# ADC.net
KiCad netlist of a schematic drawn in Altium Designer
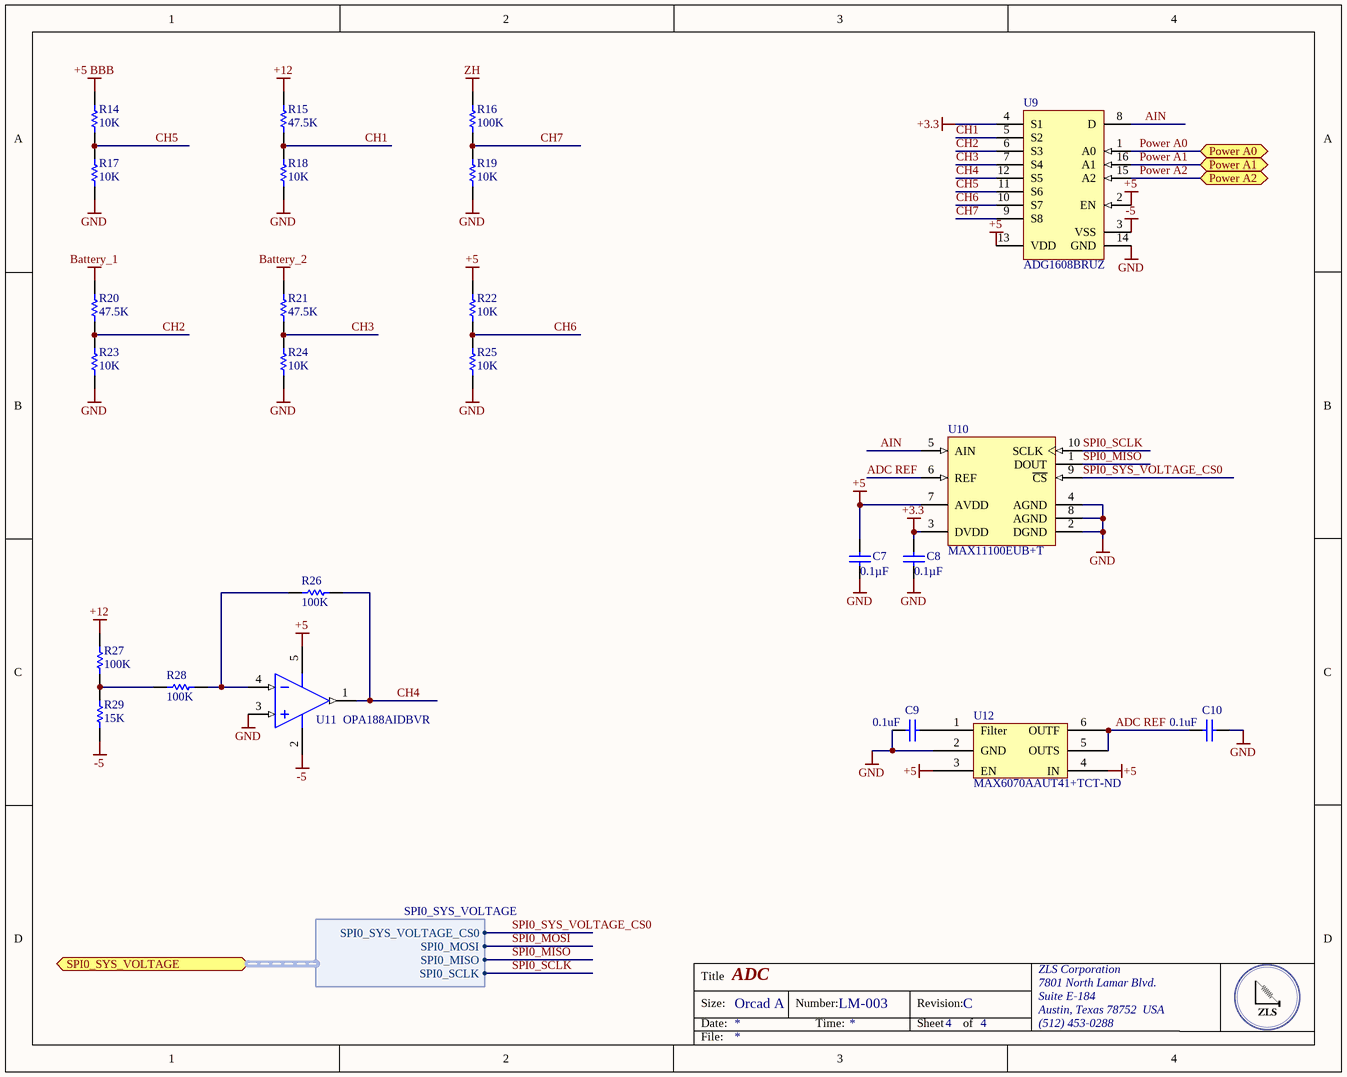
[diagram p0: ADC.SchDoc]

(export (version "E")
  (design (tool "Eeschema 10.0.6"))
  (components
    (comp (ref "C7")
      (value "CAP CER 0.1UF 25V X7R 0805")
      (footprint "CAPC0805(2012)145_N")
      (fields
        (field (name "MANUFACTURER") "Murata Electronics North America")
        (field (name "MANUFACTURER PART NUMBER") "GRM21BR71E104KA01L")
        (field (name "CAPACITANCE") "0.1µF")
        (field (name "TOLERANCE") "±10%")
      )
      (libsource (lib "Altium Content Vault") (part "CMP-1036-04795-1"))
    )
    (comp (ref "C8")
      (value "CAP CER 0.1UF 25V X7R 0805")
      (footprint "CAPC0805(2012)145_N")
      (fields
        (field (name "MANUFACTURER") "Murata Electronics North America")
        (field (name "MANUFACTURER PART NUMBER") "GRM21BR71E104KA01L")
        (field (name "CAPACITANCE") "0.1µF")
        (field (name "TOLERANCE") "±10%")
      )
      (libsource (lib "Altium Content Vault") (part "CMP-1036-04795-1"))
    )
    (comp (ref "C9")
      (value "0.1uF")
      (footprint "CAPC0402(1005)60_L")
      (description "CAP CER 0.1UF 10V X7R 0402")
      (fields
        (field (name "MANUFACTURER") "Murata Electronics North America")
        (field (name "MANUFACTURER PART NUMBER") "GRM155R71A104KA01D")
      )
      (libsource (lib "Altium Content Vault") (part "CMP-1034-00252-1"))
    )
    (comp (ref "C10")
      (value "0.1uF")
      (footprint "CAPC0402(1005)60_L")
      (description "CAP CER 0.1UF 10V X7R 0402")
      (fields
        (field (name "MANUFACTURER") "Murata Electronics North America")
        (field (name "MANUFACTURER PART NUMBER") "GRM155R71A104KA01D")
      )
      (libsource (lib "Altium Content Vault") (part "CMP-1034-00252-1"))
    )
    (comp (ref "R14")
      (value "10K")
      (footprint "RESC0805(2012)_L")
      (description "RES SMD 10K OHM 1% 1/8W 0805")
      (fields
        (field (name "MANUFACTURER") "Yageo")
        (field (name "MANUFACTURER PART NUMBER") "AT0603FRE0710KL")
      )
      (libsource (lib "Altium Content Vault") (part "CMP-1013-00215-1"))
    )
    (comp (ref "R15")
      (value "47.5K")
      (footprint "RESC0805(2012)_L")
      (description "RES SMD 47.5K OHM 1% 1/10W 0805")
      (fields
        (field (name "MANUFACTURER") "Yageo")
        (field (name "MANUFACTURER PART NUMBER") "RT0603FRE0747K5L")
      )
      (libsource (lib "Altium Content Vault") (part "CMP-1013-00215-1"))
    )
    (comp (ref "R16")
      (value "100K")
      (footprint "RESC0805(2012)_L")
      (description "RES SMD 100K OHM 1% 1/10W 0805")
      (fields
        (field (name "MANUFACTURER") "Vishay Beyschlag")
        (field (name "MANUFACTURER PART NUMBER") "MCS04020C1003FE000")
      )
      (libsource (lib "Altium Content Vault") (part "CMP-1013-00215-1"))
    )
    (comp (ref "R17")
      (value "10K")
      (footprint "RESC0805(2012)_L")
      (description "RES SMD 10K OHM 1% 1/8W 0805")
      (fields
        (field (name "MANUFACTURER") "Yageo")
        (field (name "MANUFACTURER PART NUMBER") "AT0603FRE0710KL")
      )
      (libsource (lib "Altium Content Vault") (part "CMP-1013-00215-1"))
    )
    (comp (ref "R18")
      (value "10K")
      (footprint "RESC0805(2012)_L")
      (description "RES SMD 10K OHM 1% 1/8W 0805")
      (fields
        (field (name "MANUFACTURER") "Yageo")
        (field (name "MANUFACTURER PART NUMBER") "AT0603FRE0710KL")
      )
      (libsource (lib "Altium Content Vault") (part "CMP-1013-00215-1"))
    )
    (comp (ref "R19")
      (value "10K")
      (footprint "RESC0805(2012)_L")
      (description "RES SMD 10K OHM 1% 1/8W 0805")
      (fields
        (field (name "MANUFACTURER") "Yageo")
        (field (name "MANUFACTURER PART NUMBER") "AT0603FRE0710KL")
      )
      (libsource (lib "Altium Content Vault") (part "CMP-1013-00215-1"))
    )
    (comp (ref "R20")
      (value "47.5K")
      (footprint "RESC0805(2012)_L")
      (description "RES SMD 47.5K OHM 1% 1/10W 0805")
      (fields
        (field (name "MANUFACTURER") "Yageo")
        (field (name "MANUFACTURER PART NUMBER") "RT0603FRE0747K5L")
      )
      (libsource (lib "Altium Content Vault") (part "CMP-1013-00215-1"))
    )
    (comp (ref "R21")
      (value "47.5K")
      (footprint "RESC0805(2012)_L")
      (description "RES SMD 47.5K OHM 1% 1/10W 0805")
      (fields
        (field (name "MANUFACTURER") "Yageo")
        (field (name "MANUFACTURER PART NUMBER") "RT0603FRE0747K5L")
      )
      (libsource (lib "Altium Content Vault") (part "CMP-1013-00215-1"))
    )
    (comp (ref "R22")
      (value "10K")
      (footprint "RESC0805(2012)_L")
      (description "RES SMD 10K OHM 1% 1/8W 0805")
      (fields
        (field (name "MANUFACTURER") "Yageo")
        (field (name "MANUFACTURER PART NUMBER") "AT0603FRE0710KL")
      )
      (libsource (lib "Altium Content Vault") (part "CMP-1013-00215-1"))
    )
    (comp (ref "R23")
      (value "10K")
      (footprint "RESC0805(2012)_L")
      (description "RES SMD 10K OHM 1% 1/8W 0805")
      (fields
        (field (name "MANUFACTURER") "Yageo")
        (field (name "MANUFACTURER PART NUMBER") "AT0603FRE0710KL")
      )
      (libsource (lib "Altium Content Vault") (part "CMP-1013-00215-1"))
    )
    (comp (ref "R24")
      (value "10K")
      (footprint "RESC0805(2012)_L")
      (description "RES SMD 10K OHM 1% 1/8W 0805")
      (fields
        (field (name "MANUFACTURER") "Yageo")
        (field (name "MANUFACTURER PART NUMBER") "AT0603FRE0710KL")
      )
      (libsource (lib "Altium Content Vault") (part "CMP-1013-00215-1"))
    )
    (comp (ref "R25")
      (value "10K")
      (footprint "RESC0805(2012)_L")
      (description "RES SMD 10K OHM 1% 1/8W 0805")
      (fields
        (field (name "MANUFACTURER") "Yageo")
        (field (name "MANUFACTURER PART NUMBER") "AT0603FRE0710KL")
      )
      (libsource (lib "Altium Content Vault") (part "CMP-1013-00215-1"))
    )
    (comp (ref "R26")
      (value "100K")
      (footprint "RESC0805(2012)_L")
      (description "RES SMD 100K OHM 1% 1/10W 0805")
      (fields
        (field (name "MANUFACTURER") "Vishay Beyschlag")
        (field (name "MANUFACTURER PART NUMBER") "MCS04020C1003FE000")
      )
      (libsource (lib "Altium Content Vault") (part "CMP-1013-00215-1"))
    )
    (comp (ref "R27")
      (value "100K")
      (footprint "RESC0805(2012)_L")
      (description "RES SMD 100K OHM 1% 1/10W 0805")
      (fields
        (field (name "MANUFACTURER") "Vishay Beyschlag")
        (field (name "MANUFACTURER PART NUMBER") "MCS04020C1003FE000")
      )
      (libsource (lib "Altium Content Vault") (part "CMP-1013-00215-1"))
    )
    (comp (ref "R28")
      (value "100K")
      (footprint "RESC0805(2012)_L")
      (description "RES SMD 100K OHM 1% 1/10W 0805")
      (fields
        (field (name "MANUFACTURER") "Vishay Beyschlag")
        (field (name "MANUFACTURER PART NUMBER") "MCS04020C1003FE000")
      )
      (libsource (lib "Altium Content Vault") (part "CMP-1013-00215-1"))
    )
    (comp (ref "R29")
      (value "15K")
      (footprint "RESC0805(2012)_L")
      (description "RES SMD 15K OHM 1% 1/10W 0805")
      (fields
        (field (name "MANUFACTURER") "Vishay Beyschlag")
        (field (name "MANUFACTURER PART NUMBER") "MCS04020C1502FE000")
      )
      (libsource (lib "Altium Content Vault") (part "CMP-1013-00215-1"))
    )
    (comp (ref "U9")
      (value "ADG1608BRUZ")
      (footprint "ADI-RU-16_M")
      (description "4.5 Ohm Ron, 8-Channel +/-5 V,+12 V, +5 V and +3.3 V Multiplexer, 16-pin SOP (RU-16), Tube")
      (fields (field (name "MANUFACTURER") "Analog Devices Inc.") (field (name "BASE PART NUMBER") "ADG1608"))
      (libsource (lib "Altium Content Vault") (part "CMP-0793-00136-1"))
    )
    (comp (ref "U10")
      (value "MAX11100EUB+T")
      (footprint "U10+2_L")
      (description "IC ADC 16BIT SRL 200KSPS 10UMAX")
      (fields
        (field (name "MANUFACTURER") "Maxim Integrated")
        (field (name "MANUFACTURER PART NUMBER") "MAX11100EUB+")
      )
      (libsource (lib "Altium Content Vault") (part "CMP-0249-00017-1"))
    )
    (comp (ref "U11")
      (value "OPA188AIDBVR")
      (footprint "DBV0005A_M")
      (fields (field (name "MANUFACTURER") "Texas Instruments"))
      (libsource (lib "Altium Content Vault") (part "CMP-0809-00005-2"))
    )
    (comp (ref "U12")
      (value "MAX6070AAUT41+T")
      (footprint "SOT95P280X445-6N")
      (description "IC VREF SERIES 4.096V SOT23")
      (fields
        (field (name "SUPPLIER PART NUMBER 1") "MAX6070AAUT41+TCT-ND")
        (field (name "MANUFACTURER") "Maxim Integrated")
        (field (name "TOLERANCE") "±0.04%")
      )
      (libsource (lib "ZLS_Schematic_lib") (part "MAX6070AAUT41+T"))
    )
  )
  (nets
    (net (code "2") (name "+3.3") (class "Default")
      (node (ref "C8") (pin "1") (pinfunction "1_1") (pintype "passive"))
      (node (ref "U10") (pin "3") (pinfunction "DVDD_3") (pintype "power_in"))
      (node (ref "U9") (pin "4") (pinfunction "S1_4") (pintype "passive"))
    )
    (net (code "3") (name "+5") (class "Default")
      (node (ref "C7") (pin "1") (pinfunction "1_1") (pintype "passive"))
      (node (ref "R22") (pin "1") (pinfunction "1_1") (pintype "passive"))
      (node (ref "U10") (pin "7") (pinfunction "AVDD_7") (pintype "power_in"))
      (node (ref "U11") (pin "5") (pinfunction "V+_5") (pintype "power_in"))
      (node (ref "U12") (pin "3") (pinfunction "EN_3") (pintype "passive"))
      (node (ref "U12") (pin "4") (pinfunction "IN_4") (pintype "passive"))
      (node (ref "U9") (pin "13") (pinfunction "VDD_13") (pintype "power_in"))
      (node (ref "U9") (pin "2") (pinfunction "EN_2") (pintype "input"))
    )
    (net (code "4") (name "+5 BBB") (class "Default")
      (node (ref "R14") (pin "1") (pinfunction "1_1") (pintype "passive"))
    )
    (net (code "5") (name "+12") (class "Default")
      (node (ref "R15") (pin "1") (pinfunction "1_1") (pintype "passive"))
      (node (ref "R27") (pin "1") (pinfunction "1_1") (pintype "passive"))
    )
    (net (code "6") (name "-5") (class "Default")
      (node (ref "R29") (pin "2") (pinfunction "2_2") (pintype "passive"))
      (node (ref "U11") (pin "2") (pinfunction "V-_2") (pintype "power_in"))
      (node (ref "U9") (pin "3") (pinfunction "VSS_3") (pintype "power_in"))
    )
    (net (code "7") (name "/ADC REF") (class "Default")
      (node (ref "C10") (pin "2") (pinfunction "2_2") (pintype "passive"))
      (node (ref "U10") (pin "6") (pinfunction "REF_6") (pintype "input"))
      (node (ref "U12") (pin "5") (pinfunction "OUTS_5") (pintype "passive"))
      (node (ref "U12") (pin "6") (pinfunction "OUTF_6") (pintype "passive"))
    )
    (net (code "8") (name "/AIN") (class "Default")
      (node (ref "U10") (pin "5") (pinfunction "AIN_5") (pintype "input"))
      (node (ref "U9") (pin "8") (pinfunction "D_8") (pintype "passive"))
    )
    (net (code "9") (name "/CH1") (class "Default")
      (node (ref "R15") (pin "2") (pinfunction "2_2") (pintype "passive"))
      (node (ref "R18") (pin "1") (pinfunction "1_1") (pintype "passive"))
      (node (ref "U9") (pin "5") (pinfunction "S2_5") (pintype "passive"))
    )
    (net (code "10") (name "/CH2") (class "Default")
      (node (ref "R20") (pin "2") (pinfunction "2_2") (pintype "passive"))
      (node (ref "R23") (pin "1") (pinfunction "1_1") (pintype "passive"))
      (node (ref "U9") (pin "6") (pinfunction "S3_6") (pintype "passive"))
    )
    (net (code "11") (name "/CH3") (class "Default")
      (node (ref "R21") (pin "2") (pinfunction "2_2") (pintype "passive"))
      (node (ref "R24") (pin "1") (pinfunction "1_1") (pintype "passive"))
      (node (ref "U9") (pin "7") (pinfunction "S4_7") (pintype "passive"))
    )
    (net (code "12") (name "/CH4") (class "Default")
      (node (ref "R26") (pin "2") (pinfunction "2_2") (pintype "passive"))
      (node (ref "U11") (pin "1") (pinfunction "OUT_1") (pintype "output"))
      (node (ref "U9") (pin "12") (pinfunction "S5_12") (pintype "passive"))
    )
    (net (code "13") (name "/CH5") (class "Default")
      (node (ref "R14") (pin "2") (pinfunction "2_2") (pintype "passive"))
      (node (ref "R17") (pin "1") (pinfunction "1_1") (pintype "passive"))
      (node (ref "U9") (pin "11") (pinfunction "S6_11") (pintype "passive"))
    )
    (net (code "14") (name "/CH6") (class "Default")
      (node (ref "R22") (pin "2") (pinfunction "2_2") (pintype "passive"))
      (node (ref "R25") (pin "1") (pinfunction "1_1") (pintype "passive"))
      (node (ref "U9") (pin "10") (pinfunction "S7_10") (pintype "passive"))
    )
    (net (code "15") (name "/CH7") (class "Default")
      (node (ref "R16") (pin "2") (pinfunction "2_2") (pintype "passive"))
      (node (ref "R19") (pin "1") (pinfunction "1_1") (pintype "passive"))
      (node (ref "U9") (pin "9") (pinfunction "S8_9") (pintype "passive"))
    )
    (net (code "16") (name "/Power A0") (class "Default")
      (node (ref "U9") (pin "1") (pinfunction "A0_1") (pintype "input"))
    )
    (net (code "17") (name "/Power A1") (class "Default")
      (node (ref "U9") (pin "16") (pinfunction "A1_16") (pintype "input"))
    )
    (net (code "18") (name "/Power A2") (class "Default")
      (node (ref "U9") (pin "15") (pinfunction "A2_15") (pintype "input"))
    )
    (net (code "19") (name "/SPI0_MISO") (class "Default")
      (node (ref "U10") (pin "1") (pinfunction "DOUT_1") (pintype "tri_state"))
    )
    (net (code "21") (name "/SPI0_SCLK") (class "Default")
      (node (ref "U10") (pin "10") (pinfunction "SCLK_10") (pintype "input"))
    )
    (net (code "22") (name "/SPI0_SYS_VOLTAGE_CS0") (class "Default")
      (node (ref "U10") (pin "9") (pinfunction "~{CS}_9") (pintype "input"))
    )
    (net (code "24") (name "Battery_1") (class "Default")
      (node (ref "R20") (pin "1") (pinfunction "1_1") (pintype "passive"))
    )
    (net (code "25") (name "Battery_2") (class "Default")
      (node (ref "R21") (pin "1") (pinfunction "1_1") (pintype "passive"))
    )
    (net (code "26") (name "GND") (class "Default")
      (node (ref "C10") (pin "1") (pinfunction "1_1") (pintype "passive"))
      (node (ref "C7") (pin "2") (pinfunction "2_2") (pintype "passive"))
      (node (ref "C8") (pin "2") (pinfunction "2_2") (pintype "passive"))
      (node (ref "C9") (pin "2") (pinfunction "2_2") (pintype "passive"))
      (node (ref "R17") (pin "2") (pinfunction "2_2") (pintype "passive"))
      (node (ref "R18") (pin "2") (pinfunction "2_2") (pintype "passive"))
      (node (ref "R19") (pin "2") (pinfunction "2_2") (pintype "passive"))
      (node (ref "R23") (pin "2") (pinfunction "2_2") (pintype "passive"))
      (node (ref "R24") (pin "2") (pinfunction "2_2") (pintype "passive"))
      (node (ref "R25") (pin "2") (pinfunction "2_2") (pintype "passive"))
      (node (ref "U10") (pin "2") (pinfunction "DGND_2") (pintype "power_in"))
      (node (ref "U10") (pin "4") (pinfunction "AGND_4") (pintype "power_in"))
      (node (ref "U10") (pin "8") (pinfunction "AGND_8") (pintype "power_in"))
      (node (ref "U11") (pin "3") (pinfunction "IN+_3") (pintype "input"))
      (node (ref "U12") (pin "2") (pinfunction "GND_2") (pintype "passive"))
      (node (ref "U9") (pin "14") (pinfunction "GND_14") (pintype "power_in"))
    )
    (net (code "27") (name "Net-(R27-Pad2)") (class "Default")
      (node (ref "R27") (pin "2") (pinfunction "2_2") (pintype "passive"))
      (node (ref "R28") (pin "1") (pinfunction "1_1") (pintype "passive"))
      (node (ref "R29") (pin "1") (pinfunction "1_1") (pintype "passive"))
    )
    (net (code "28") (name "Net-(U11-IN-)") (class "Default")
      (node (ref "R26") (pin "1") (pinfunction "1_1") (pintype "passive"))
      (node (ref "R28") (pin "2") (pinfunction "2_2") (pintype "passive"))
      (node (ref "U11") (pin "4") (pinfunction "IN-_4") (pintype "input"))
    )
    (net (code "29") (name "Net-(U12-Filter)") (class "Default")
      (node (ref "C9") (pin "1") (pinfunction "1_1") (pintype "passive"))
      (node (ref "U12") (pin "1") (pinfunction "Filter_1") (pintype "passive"))
    )
    (net (code "30") (name "ZH") (class "Default")
      (node (ref "R16") (pin "1") (pinfunction "1_1") (pintype "passive"))
    )
  )
)
